# WX0_010_218DL.net
KiCad netlist of a schematic drawn in Altium Designer
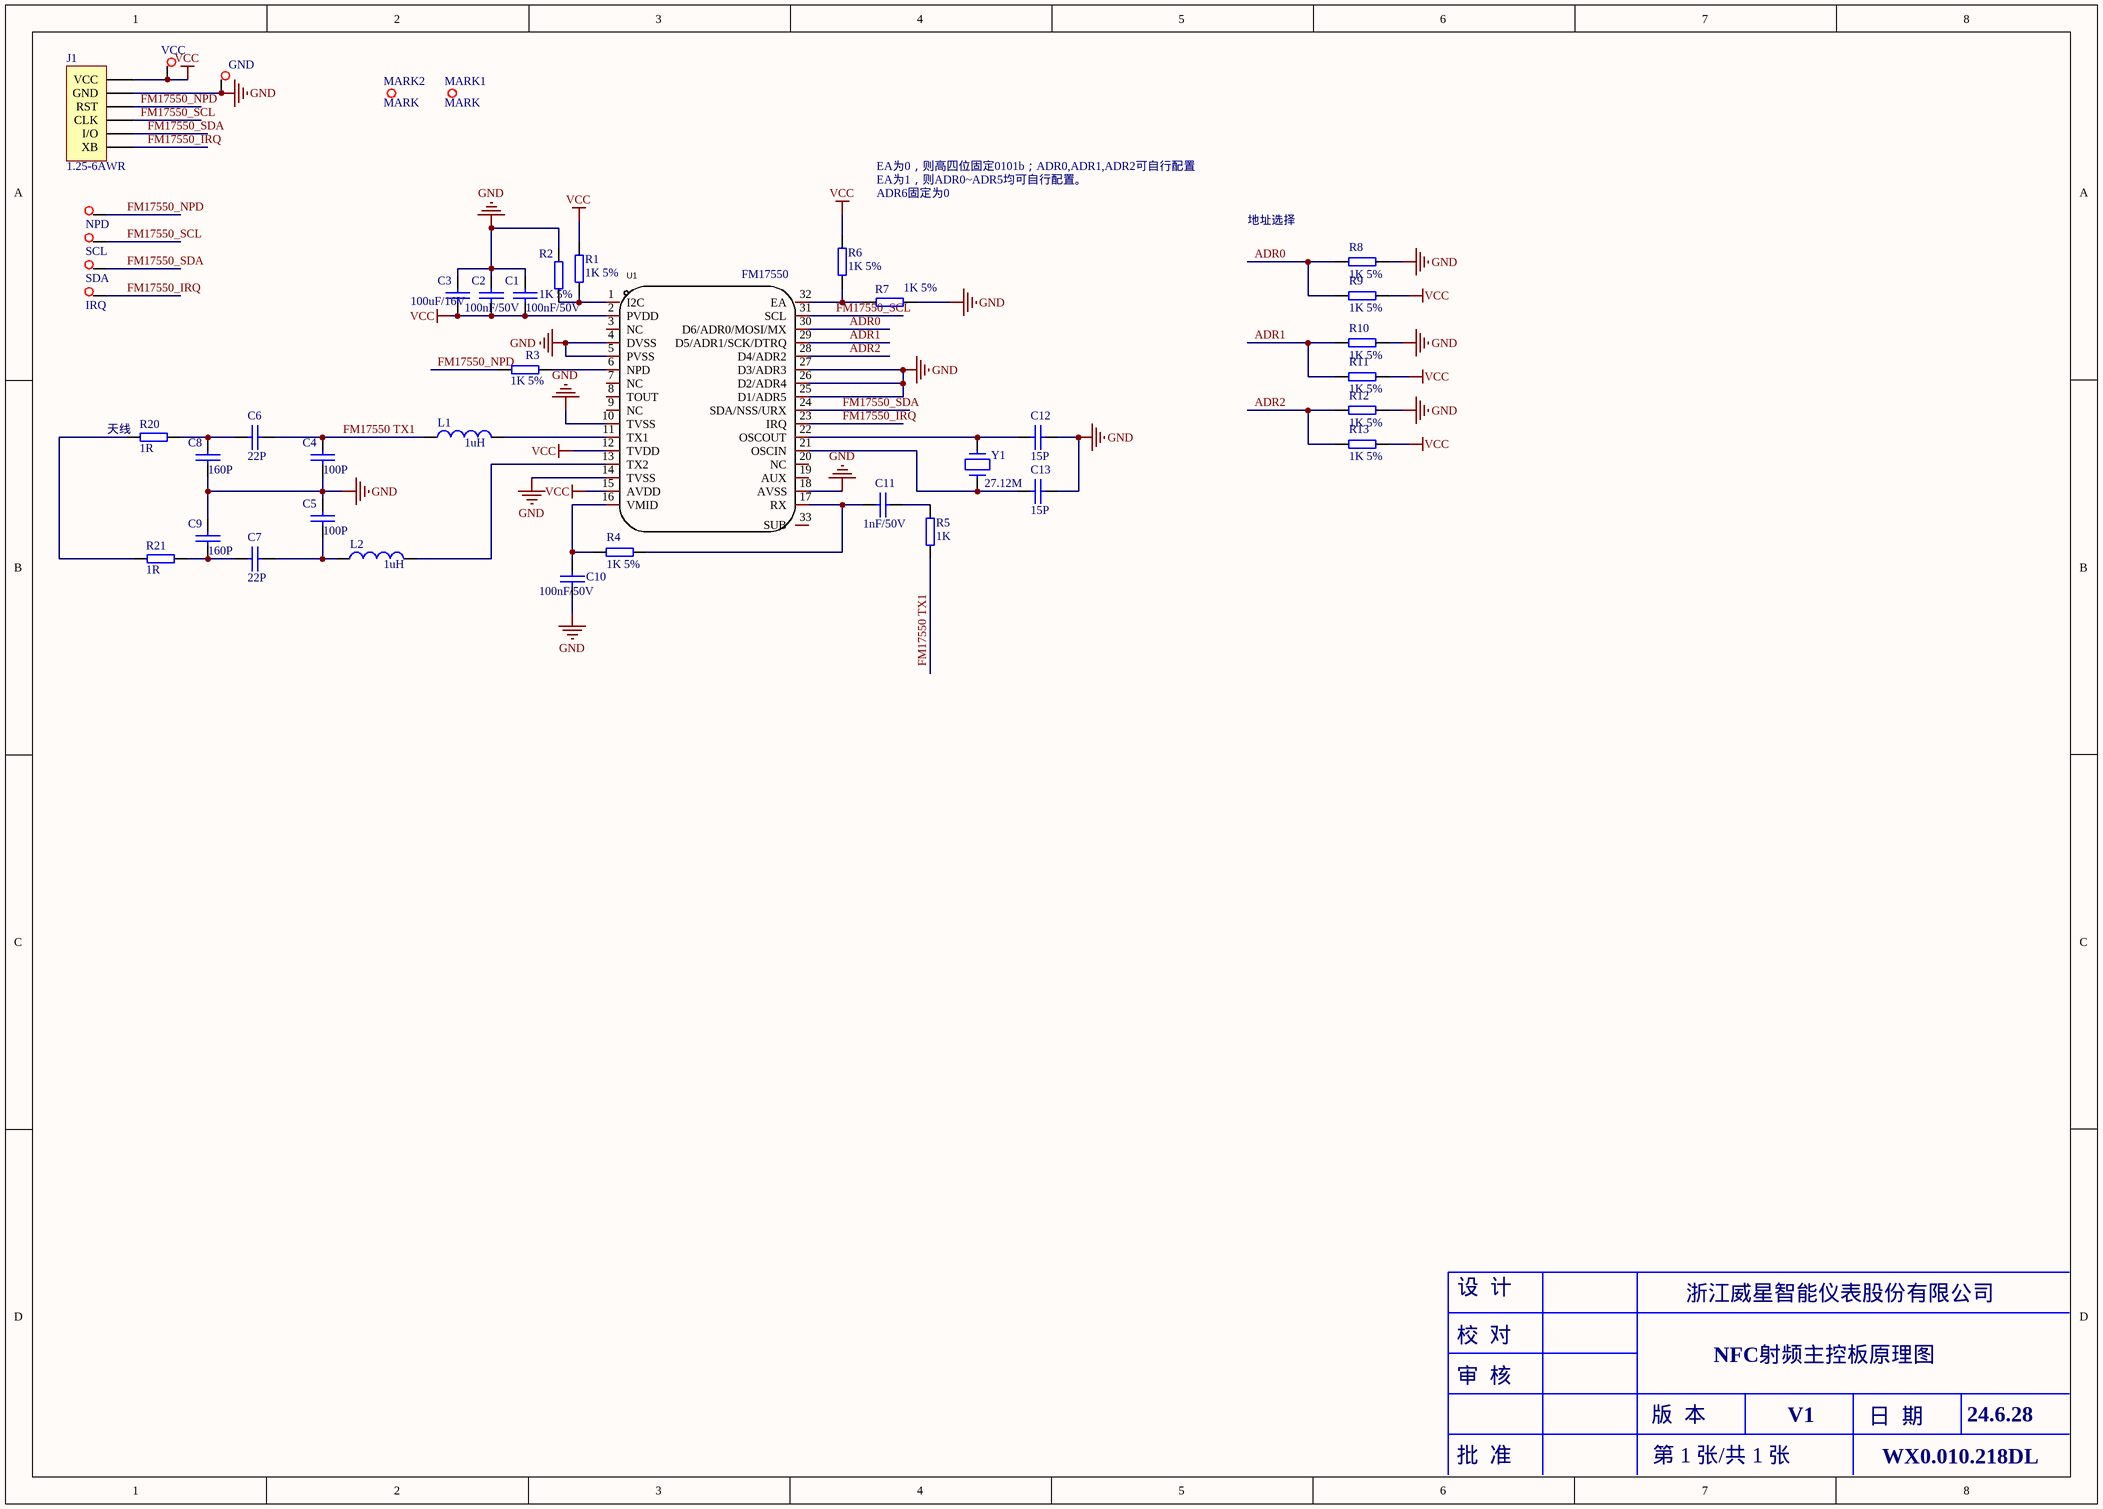
[diagram p0: WX0.010.218DL.SchDoc]

(export (version "E")
  (design (tool "Eeschema 10.0.6"))
  (components
    (comp (ref "C1")
      (value "100nF/50V")
      (footprint "CAP0603")
      (description "104pF,50 V,±10%,0603,国巨,CC0603KRX7R9BB104")
      (fields (field (name "PART NUMBER") "101020103-0021"))
      (libsource (lib "Database_Libs2") (part "CC03K7R9_100N"))
    )
    (comp (ref "C2")
      (value "100nF/50V")
      (footprint "CAP0603")
      (description "104pF,50 V,±10%,0603,国巨,CC0603KRX7R9BB104")
      (fields (field (name "PART NUMBER") "101020103-0021"))
      (libsource (lib "Database_Libs2") (part "CC03K7R9_100N"))
    )
    (comp (ref "C3")
      (value "100uF/16V")
      (footprint "GRM31CR60J107ME39L")
      (description "100u,16 V,±10%,1206,国巨,CC1206KRNPO7BN106P")
      (libsource (lib "Database_Libs2") (part "CC06KPO7_106P"))
    )
    (comp (ref "C4")
      (value "100P")
      (footprint "CAP0603")
      (description "104pF,50 V,±10%,0603,国巨,CC0603KRX7R9BB104")
      (fields (field (name "PART NUMBER") "101020103-0021"))
      (libsource (lib "Database_Libs2") (part "CC03K7R9_100N"))
    )
    (comp (ref "C5")
      (value "100P")
      (footprint "CAP0603")
      (description "104pF,50 V,±10%,0603,国巨,CC0603KRX7R9BB104")
      (fields (field (name "PART NUMBER") "101020103-0021"))
      (libsource (lib "Database_Libs2") (part "CC03K7R9_100N"))
    )
    (comp (ref "C6")
      (value "22P")
      (footprint "CAP0603")
      (description "104pF,50 V,±10%,0603,国巨,CC0603KRX7R9BB104")
      (fields (field (name "PART NUMBER") "101020103-0021"))
      (libsource (lib "Database_Libs2") (part "CC03K7R9_100N"))
    )
    (comp (ref "C7")
      (value "22P")
      (footprint "CAP0603")
      (description "104pF,50 V,±10%,0603,国巨,CC0603KRX7R9BB104")
      (fields (field (name "PART NUMBER") "101020103-0021"))
      (libsource (lib "Database_Libs2") (part "CC03K7R9_100N"))
    )
    (comp (ref "C8")
      (value "160P")
      (footprint "CAP0603")
      (description "104pF,50 V,±10%,0603,国巨,CC0603KRX7R9BB104")
      (fields (field (name "PART NUMBER") "101020103-0021"))
      (libsource (lib "Database_Libs2") (part "CC03K7R9_100N"))
    )
    (comp (ref "C9")
      (value "160P")
      (footprint "CAP0603")
      (description "104pF,50 V,±10%,0603,国巨,CC0603KRX7R9BB104")
      (fields (field (name "PART NUMBER") "101020103-0021"))
      (libsource (lib "Database_Libs2") (part "CC03K7R9_100N"))
    )
    (comp (ref "C10")
      (value "100nF/50V")
      (footprint "CAP0603")
      (description "104pF,50 V,±10%,0603,国巨,CC0603KRX7R9BB104")
      (fields (field (name "PART NUMBER") "101020103-0021"))
      (libsource (lib "Database_Libs2") (part "CC03K7R9_100N"))
    )
    (comp (ref "C11")
      (value "1nF/50V")
      (footprint "CAP0603")
      (description "104pF,50 V,±10%,0603,国巨,CC0603KRX7R9BB104")
      (fields (field (name "PART NUMBER") "101020103-0021"))
      (libsource (lib "Database_Libs2") (part "CC03K7R9_100N"))
    )
    (comp (ref "C12")
      (value "15P")
      (footprint "CAP0603")
      (description "104pF,50 V,±10%,0603,国巨,CC0603KRX7R9BB104")
      (fields (field (name "PART NUMBER") "101020103-0021"))
      (libsource (lib "Database_Libs2") (part "CC03K7R9_100N"))
    )
    (comp (ref "C13")
      (value "15P")
      (footprint "CAP0603")
      (description "104pF,50 V,±10%,0603,国巨,CC0603KRX7R9BB104")
      (fields (field (name "PART NUMBER") "101020103-0021"))
      (libsource (lib "Database_Libs2") (part "CC03K7R9_100N"))
    )
    (comp (ref "GND")
      (value "TEST-PAD")
      (footprint "TEST-PAD")
      (description "单面焊盘测试点")
      (fields (field (name "PART NUMBER") "AD_WXHJ_TEST-PAD_01"))
      (libsource (lib "Database_Libs2") (part "TEST-PAD"))
    )
    (comp (ref "IRQ")
      (value "TEST-PAD")
      (footprint "TEST-PAD")
      (description "单面焊盘测试点")
      (fields (field (name "PART NUMBER") "AD_WXHJ_TEST-PAD_01"))
      (libsource (lib "Database_Libs2") (part "TEST-PAD"))
    )
    (comp (ref "J1")
      (value "1.25-6AWR")
      (footprint "SMT-1.25-6")
      (description "1.25-6AWR 卷,6针1.25mm,母头,单排,贴片卧式")
      (fields (field (name "PART NUMBER") "1010902-0121"))
      (libsource (lib "Database_Libs2") (part "CARD1608"))
    )
    (comp (ref "L1")
      (value "1uH")
      (footprint "L0805")
      (description "Inductor")
      (fields (field (name "PUBLISHER") "Altium Limited"))
      (libsource (lib "Miscellaneous Devices") (part "Inductor"))
    )
    (comp (ref "L2")
      (value "1uH")
      (footprint "L0805")
      (description "Inductor")
      (fields (field (name "PUBLISHER") "Altium Limited"))
      (libsource (lib "Miscellaneous Devices") (part "Inductor"))
    )
    (comp (ref "MARK1")
      (value "MARK")
      (footprint "MARK")
      (description "MARK点")
      (fields (field (name "PART NUMBER") "AD_WXHJ_MARK_01"))
      (libsource (lib "Database_Libs2") (part "MARK"))
    )
    (comp (ref "MARK2")
      (value "MARK")
      (footprint "MARK")
      (description "MARK点")
      (fields (field (name "PART NUMBER") "AD_WXHJ_MARK_01"))
      (libsource (lib "Database_Libs2") (part "MARK"))
    )
    (comp (ref "NPD")
      (value "TEST-PAD")
      (footprint "TEST-PAD")
      (description "单面焊盘测试点")
      (fields (field (name "PART NUMBER") "AD_WXHJ_TEST-PAD_01"))
      (libsource (lib "Database_Libs2") (part "TEST-PAD"))
    )
    (comp (ref "R1")
      (value "1K 5%")
      (footprint "RES0603")
      (description "1K,±5%,1/10W,0603,国巨,RC0603JR-071KL")
      (fields (field (name "PART NUMBER") "101010103-0008"))
      (libsource (lib "Database_Libs2") (part "RC03J_1K"))
    )
    (comp (ref "R2")
      (value "1K 5%")
      (footprint "RES0603")
      (description "1K,±5%,1/10W,0603,国巨,RC0603JR-071KL")
      (fields (field (name "PART NUMBER") "101010103-0008"))
      (libsource (lib "Database_Libs2") (part "RC03J_1K"))
    )
    (comp (ref "R3")
      (value "1K 5%")
      (footprint "RES0603")
      (description "1K,±5%,1/10W,0603,国巨,RC0603JR-071KL")
      (fields (field (name "PART NUMBER") "101010103-0008"))
      (libsource (lib "Database_Libs2") (part "RC03J_1K"))
    )
    (comp (ref "R4")
      (value "1K 5%")
      (footprint "RES0603")
      (description "1K,±5%,1/10W,0603,国巨,RC0603JR-071KL")
      (fields (field (name "PART NUMBER") "101010103-0008"))
      (libsource (lib "Database_Libs2") (part "RC03J_1K"))
    )
    (comp (ref "R5")
      (value "1K")
      (footprint "RES0603")
      (description "1K,±5%,1/10W,0603,国巨,RC0603JR-071KL")
      (fields (field (name "PART NUMBER") "101010103-0008"))
      (libsource (lib "Database_Libs2") (part "RC03J_1K"))
    )
    (comp (ref "R6")
      (value "1K 5%")
      (footprint "RES0603")
      (description "1K,±5%,1/10W,0603,国巨,RC0603JR-071KL")
      (fields (field (name "PART NUMBER") "101010103-0008"))
      (libsource (lib "Database_Libs2") (part "RC03J_1K"))
    )
    (comp (ref "R7")
      (value "1K 5%")
      (footprint "RES0603")
      (description "1K,±5%,1/10W,0603,国巨,RC0603JR-071KL")
      (fields (field (name "PART NUMBER") "101010103-0008"))
      (libsource (lib "Database_Libs2") (part "RC03J_1K"))
    )
    (comp (ref "R8")
      (value "1K 5%")
      (footprint "RES0603")
      (description "1K,±5%,1/10W,0603,国巨,RC0603JR-071KL")
      (fields (field (name "PART NUMBER") "101010103-0008"))
      (libsource (lib "Database_Libs2") (part "RC03J_1K"))
    )
    (comp (ref "R9")
      (value "1K 5%")
      (footprint "RES0603")
      (description "1K,±5%,1/10W,0603,国巨,RC0603JR-071KL")
      (fields (field (name "PART NUMBER") "101010103-0008"))
      (libsource (lib "Database_Libs2") (part "RC03J_1K"))
    )
    (comp (ref "R10")
      (value "1K 5%")
      (footprint "RES0603")
      (description "1K,±5%,1/10W,0603,国巨,RC0603JR-071KL")
      (fields (field (name "PART NUMBER") "101010103-0008"))
      (libsource (lib "Database_Libs2") (part "RC03J_1K"))
    )
    (comp (ref "R11")
      (value "1K 5%")
      (footprint "RES0603")
      (description "1K,±5%,1/10W,0603,国巨,RC0603JR-071KL")
      (fields (field (name "PART NUMBER") "101010103-0008"))
      (libsource (lib "Database_Libs2") (part "RC03J_1K"))
    )
    (comp (ref "R12")
      (value "1K 5%")
      (footprint "RES0603")
      (description "1K,±5%,1/10W,0603,国巨,RC0603JR-071KL")
      (fields (field (name "PART NUMBER") "101010103-0008"))
      (libsource (lib "Database_Libs2") (part "RC03J_1K"))
    )
    (comp (ref "R13")
      (value "1K 5%")
      (footprint "RES0603")
      (description "1K,±5%,1/10W,0603,国巨,RC0603JR-071KL")
      (fields (field (name "PART NUMBER") "101010103-0008"))
      (libsource (lib "Database_Libs2") (part "RC03J_1K"))
    )
    (comp (ref "R20")
      (value "1R")
      (footprint "RES0603")
      (description "国巨,±5%,0603,,155 ℃,-55 ℃,RC0603J2-070RL,无铅,200 ppm/℃,1/10W,,0R")
      (fields (field (name "PART NUMBER") "101010103-0001"))
      (libsource (lib "Database_Libs2") (part "RC03J_10K"))
    )
    (comp (ref "R21")
      (value "1R")
      (footprint "RES0603")
      (description "国巨,±5%,0603,,155 ℃,-55 ℃,RC0603J2-070RL,无铅,200 ppm/℃,1/10W,,0R")
      (fields (field (name "PART NUMBER") "101010103-0001"))
      (libsource (lib "Database_Libs2") (part "RC03J_10K"))
    )
    (comp (ref "SCL")
      (value "TEST-PAD")
      (footprint "TEST-PAD")
      (description "单面焊盘测试点")
      (fields (field (name "PART NUMBER") "AD_WXHJ_TEST-PAD_01"))
      (libsource (lib "Database_Libs2") (part "TEST-PAD"))
    )
    (comp (ref "SDA")
      (value "TEST-PAD")
      (footprint "TEST-PAD")
      (description "单面焊盘测试点")
      (fields (field (name "PART NUMBER") "AD_WXHJ_TEST-PAD_01"))
      (libsource (lib "Database_Libs2") (part "TEST-PAD"))
    )
    (comp (ref "U1")
      (value "FM17550")
      (footprint "QFN-32_L5.0-W5.0-P0.50-BL-EP3.7")
      (fields (field (name "MANUFACTURER") "FM(����΢)"))
      (libsource (lib "FM175501_FM17550.schdoc") (part "FM17550"))
    )
    (comp (ref "VCC")
      (value "TEST-PAD")
      (footprint "TEST-PAD")
      (description "单面焊盘测试点")
      (fields (field (name "PART NUMBER") "AD_WXHJ_TEST-PAD_01"))
      (libsource (lib "Database_Libs2") (part "TEST-PAD"))
    )
    (comp (ref "Y1")
      (value "27.12M")
      (footprint "SX-3225")
      (fields (field (name "PART NUMBER") "1010601-0009"))
      (libsource (lib "PCB_Project1") (part "04_XTALSG12MD_32.768kD"))
    )
  )
  (nets
    (net (code "1") (name "/ADR0") (class "Default")
      (node (ref "R8") (pin "1") (pinfunction "1_1") (pintype "passive"))
      (node (ref "R9") (pin "1") (pinfunction "1_1") (pintype "passive"))
      (node (ref "U1") (pin "30") (pinfunction "D6/ADR0/MOSI/MX_30") (pintype "passive"))
    )
    (net (code "2") (name "/ADR1") (class "Default")
      (node (ref "R10") (pin "1") (pinfunction "1_1") (pintype "passive"))
      (node (ref "R11") (pin "1") (pinfunction "1_1") (pintype "passive"))
      (node (ref "U1") (pin "29") (pinfunction "D5/ADR1/SCK/DTRQ_29") (pintype "passive"))
    )
    (net (code "3") (name "/ADR2") (class "Default")
      (node (ref "R12") (pin "1") (pinfunction "1_1") (pintype "passive"))
      (node (ref "R13") (pin "1") (pinfunction "1_1") (pintype "passive"))
      (node (ref "U1") (pin "28") (pinfunction "D4/ADR2_28") (pintype "passive"))
    )
    (net (code "4") (name "/FM17550 TX1") (class "Default")
      (node (ref "C4") (pin "2") (pinfunction "2_2") (pintype "passive"))
      (node (ref "C6") (pin "1") (pinfunction "1_1") (pintype "passive"))
      (node (ref "L1") (pin "1") (pinfunction "1_1") (pintype "passive"))
      (node (ref "R5") (pin "1") (pinfunction "1_1") (pintype "passive"))
    )
    (net (code "5") (name "/FM17550_IRQ") (class "Default")
      (node (ref "IRQ") (pin "1") (pinfunction "1_1") (pintype "passive"))
      (node (ref "J1") (pin "1") (pinfunction "XB_1") (pintype "passive"))
      (node (ref "U1") (pin "23") (pinfunction "IRQ_23") (pintype "passive"))
    )
    (net (code "6") (name "/FM17550_NPD") (class "Default")
      (node (ref "J1") (pin "4") (pinfunction "RST_4") (pintype "passive"))
      (node (ref "NPD") (pin "1") (pinfunction "1_1") (pintype "passive"))
      (node (ref "R3") (pin "2") (pinfunction "2_2") (pintype "passive"))
    )
    (net (code "7") (name "/FM17550_SCL") (class "Default")
      (node (ref "J1") (pin "3") (pinfunction "CLK_3") (pintype "passive"))
      (node (ref "SCL") (pin "1") (pinfunction "1_1") (pintype "passive"))
      (node (ref "U1") (pin "31") (pinfunction "SCL_31") (pintype "passive"))
    )
    (net (code "8") (name "/FM17550_SDA") (class "Default")
      (node (ref "J1") (pin "2") (pinfunction "I/O_2") (pintype "passive"))
      (node (ref "SDA") (pin "1") (pinfunction "1_1") (pintype "passive"))
      (node (ref "U1") (pin "24") (pinfunction "SDA/NSS/URX_24") (pintype "passive"))
    )
    (net (code "9") (name "GND") (class "Default")
      (node (ref "C1") (pin "2") (pinfunction "2_2") (pintype "passive"))
      (node (ref "C10") (pin "2") (pinfunction "2_2") (pintype "passive"))
      (node (ref "C12") (pin "2") (pinfunction "2_2") (pintype "passive"))
      (node (ref "C13") (pin "2") (pinfunction "2_2") (pintype "passive"))
      (node (ref "C2") (pin "2") (pinfunction "2_2") (pintype "passive"))
      (node (ref "C3") (pin "1") (pinfunction "1_1") (pintype "passive"))
      (node (ref "C4") (pin "1") (pinfunction "1_1") (pintype "passive"))
      (node (ref "C5") (pin "2") (pinfunction "2_2") (pintype "passive"))
      (node (ref "C8") (pin "1") (pinfunction "1_1") (pintype "passive"))
      (node (ref "C9") (pin "2") (pinfunction "2_2") (pintype "passive"))
      (node (ref "GND") (pin "1") (pinfunction "1_1") (pintype "passive"))
      (node (ref "J1") (pin "5") (pinfunction "GND_5") (pintype "passive"))
      (node (ref "R10") (pin "2") (pinfunction "2_2") (pintype "passive"))
      (node (ref "R12") (pin "2") (pinfunction "2_2") (pintype "passive"))
      (node (ref "R2") (pin "2") (pinfunction "2_2") (pintype "passive"))
      (node (ref "R7") (pin "1") (pinfunction "1_1") (pintype "passive"))
      (node (ref "R8") (pin "2") (pinfunction "2_2") (pintype "passive"))
      (node (ref "U1") (pin "10") (pinfunction "TVSS_10") (pintype "passive"))
      (node (ref "U1") (pin "14") (pinfunction "TVSS_14") (pintype "passive"))
      (node (ref "U1") (pin "18") (pinfunction "AVSS_18") (pintype "passive"))
      (node (ref "U1") (pin "25") (pinfunction "D1/ADR5_25") (pintype "passive"))
      (node (ref "U1") (pin "26") (pinfunction "D2/ADR4_26") (pintype "passive"))
      (node (ref "U1") (pin "27") (pinfunction "D3/ADR3_27") (pintype "passive"))
      (node (ref "U1") (pin "4") (pinfunction "DVSS_4") (pintype "passive"))
      (node (ref "U1") (pin "5") (pinfunction "PVSS_5") (pintype "passive"))
    )
    (net (code "10") (name "Net-(C5-Pad1)") (class "Default")
      (node (ref "C5") (pin "1") (pinfunction "1_1") (pintype "passive"))
      (node (ref "C7") (pin "1") (pinfunction "1_1") (pintype "passive"))
      (node (ref "L2") (pin "1") (pinfunction "1_1") (pintype "passive"))
    )
    (net (code "11") (name "Net-(C6-Pad2)") (class "Default")
      (node (ref "C6") (pin "2") (pinfunction "2_2") (pintype "passive"))
      (node (ref "C8") (pin "2") (pinfunction "2_2") (pintype "passive"))
      (node (ref "R20") (pin "1") (pinfunction "1_1") (pintype "passive"))
    )
    (net (code "12") (name "Net-(C7-Pad2)") (class "Default")
      (node (ref "C7") (pin "2") (pinfunction "2_2") (pintype "passive"))
      (node (ref "C9") (pin "1") (pinfunction "1_1") (pintype "passive"))
      (node (ref "R21") (pin "1") (pinfunction "1_1") (pintype "passive"))
    )
    (net (code "13") (name "Net-(C11-Pad2)") (class "Default")
      (node (ref "C11") (pin "2") (pinfunction "2_2") (pintype "passive"))
      (node (ref "R5") (pin "2") (pinfunction "2_2") (pintype "passive"))
    )
    (net (code "14") (name "Net-(R20-Pad2)") (class "Default")
      (node (ref "R20") (pin "2") (pinfunction "2_2") (pintype "passive"))
      (node (ref "R21") (pin "2") (pinfunction "2_2") (pintype "passive"))
    )
    (net (code "15") (name "Net-(U1-EA)") (class "Default")
      (node (ref "R6") (pin "2") (pinfunction "2_2") (pintype "passive"))
      (node (ref "R7") (pin "2") (pinfunction "2_2") (pintype "passive"))
      (node (ref "U1") (pin "32") (pinfunction "EA_32") (pintype "passive"))
    )
    (net (code "16") (name "Net-(U1-I2C)") (class "Default")
      (node (ref "R1") (pin "1") (pinfunction "1_1") (pintype "passive"))
      (node (ref "R2") (pin "1") (pinfunction "1_1") (pintype "passive"))
      (node (ref "U1") (pin "1") (pinfunction "I2C_1") (pintype "passive"))
    )
    (net (code "17") (name "Net-(U1-NPD)") (class "Default")
      (node (ref "R3") (pin "1") (pinfunction "1_1") (pintype "passive"))
      (node (ref "U1") (pin "6") (pinfunction "NPD_6") (pintype "passive"))
    )
    (net (code "18") (name "Net-(U1-OSCIN)") (class "Default")
      (node (ref "C13") (pin "1") (pinfunction "1_1") (pintype "passive"))
      (node (ref "U1") (pin "21") (pinfunction "OSCIN_21") (pintype "passive"))
      (node (ref "Y1") (pin "1") (pinfunction "1_1") (pintype "passive"))
    )
    (net (code "19") (name "Net-(U1-OSCOUT)") (class "Default")
      (node (ref "C12") (pin "1") (pinfunction "1_1") (pintype "passive"))
      (node (ref "U1") (pin "22") (pinfunction "OSCOUT_22") (pintype "passive"))
      (node (ref "Y1") (pin "3") (pinfunction "3_3") (pintype "passive"))
    )
    (net (code "20") (name "Net-(U1-RX)") (class "Default")
      (node (ref "C11") (pin "1") (pinfunction "1_1") (pintype "passive"))
      (node (ref "R4") (pin "2") (pinfunction "2_2") (pintype "passive"))
      (node (ref "U1") (pin "17") (pinfunction "RX_17") (pintype "passive"))
    )
    (net (code "21") (name "Net-(U1-TX1)") (class "Default")
      (node (ref "L1") (pin "2") (pinfunction "2_2") (pintype "passive"))
      (node (ref "U1") (pin "11") (pinfunction "TX1_11") (pintype "passive"))
    )
    (net (code "22") (name "Net-(U1-TX2)") (class "Default")
      (node (ref "L2") (pin "2") (pinfunction "2_2") (pintype "passive"))
      (node (ref "U1") (pin "13") (pinfunction "TX2_13") (pintype "passive"))
    )
    (net (code "23") (name "Net-(U1-VMID)") (class "Default")
      (node (ref "C10") (pin "1") (pinfunction "1_1") (pintype "passive"))
      (node (ref "R4") (pin "1") (pinfunction "1_1") (pintype "passive"))
      (node (ref "U1") (pin "16") (pinfunction "VMID_16") (pintype "passive"))
    )
    (net (code "24") (name "VCC") (class "Default")
      (node (ref "C1") (pin "1") (pinfunction "1_1") (pintype "passive"))
      (node (ref "C2") (pin "1") (pinfunction "1_1") (pintype "passive"))
      (node (ref "C3") (pin "2") (pinfunction "2_2") (pintype "passive"))
      (node (ref "J1") (pin "6") (pinfunction "VCC_6") (pintype "passive"))
      (node (ref "R1") (pin "2") (pinfunction "2_2") (pintype "passive"))
      (node (ref "R11") (pin "2") (pinfunction "2_2") (pintype "passive"))
      (node (ref "R13") (pin "2") (pinfunction "2_2") (pintype "passive"))
      (node (ref "R6") (pin "1") (pinfunction "1_1") (pintype "passive"))
      (node (ref "R9") (pin "2") (pinfunction "2_2") (pintype "passive"))
      (node (ref "U1") (pin "12") (pinfunction "TVDD_12") (pintype "passive"))
      (node (ref "U1") (pin "15") (pinfunction "AVDD_15") (pintype "passive"))
      (node (ref "U1") (pin "2") (pinfunction "PVDD_2") (pintype "passive"))
      (node (ref "VCC") (pin "1") (pinfunction "1_1") (pintype "passive"))
    )
    (net (code "25") (name "unconnected-(U1-AUX-Pad19)") (class "Default")
      (node (ref "U1") (pin "19") (pinfunction "AUX_19") (pintype "passive"))
    )
    (net (code "26") (name "unconnected-(U1-NC-Pad3)") (class "Default")
      (node (ref "U1") (pin "3") (pinfunction "NC_3") (pintype "passive"))
    )
    (net (code "27") (name "unconnected-(U1-NC-Pad7)") (class "Default")
      (node (ref "U1") (pin "7") (pinfunction "NC_7") (pintype "passive"))
    )
    (net (code "28") (name "unconnected-(U1-NC-Pad9)") (class "Default")
      (node (ref "U1") (pin "9") (pinfunction "NC_9") (pintype "passive"))
    )
    (net (code "29") (name "unconnected-(U1-NC-Pad20)") (class "Default")
      (node (ref "U1") (pin "20") (pinfunction "NC_20") (pintype "passive"))
    )
    (net (code "30") (name "unconnected-(U1-SUB-Pad33)") (class "Default")
      (node (ref "U1") (pin "33") (pinfunction "SUB_33") (pintype "passive"))
    )
    (net (code "31") (name "unconnected-(U1-TOUT-Pad8)") (class "Default")
      (node (ref "U1") (pin "8") (pinfunction "TOUT_8") (pintype "passive"))
    )
  )
)
